# Flight_Computer.net
KiCad netlist of a schematic drawn in EAGLE
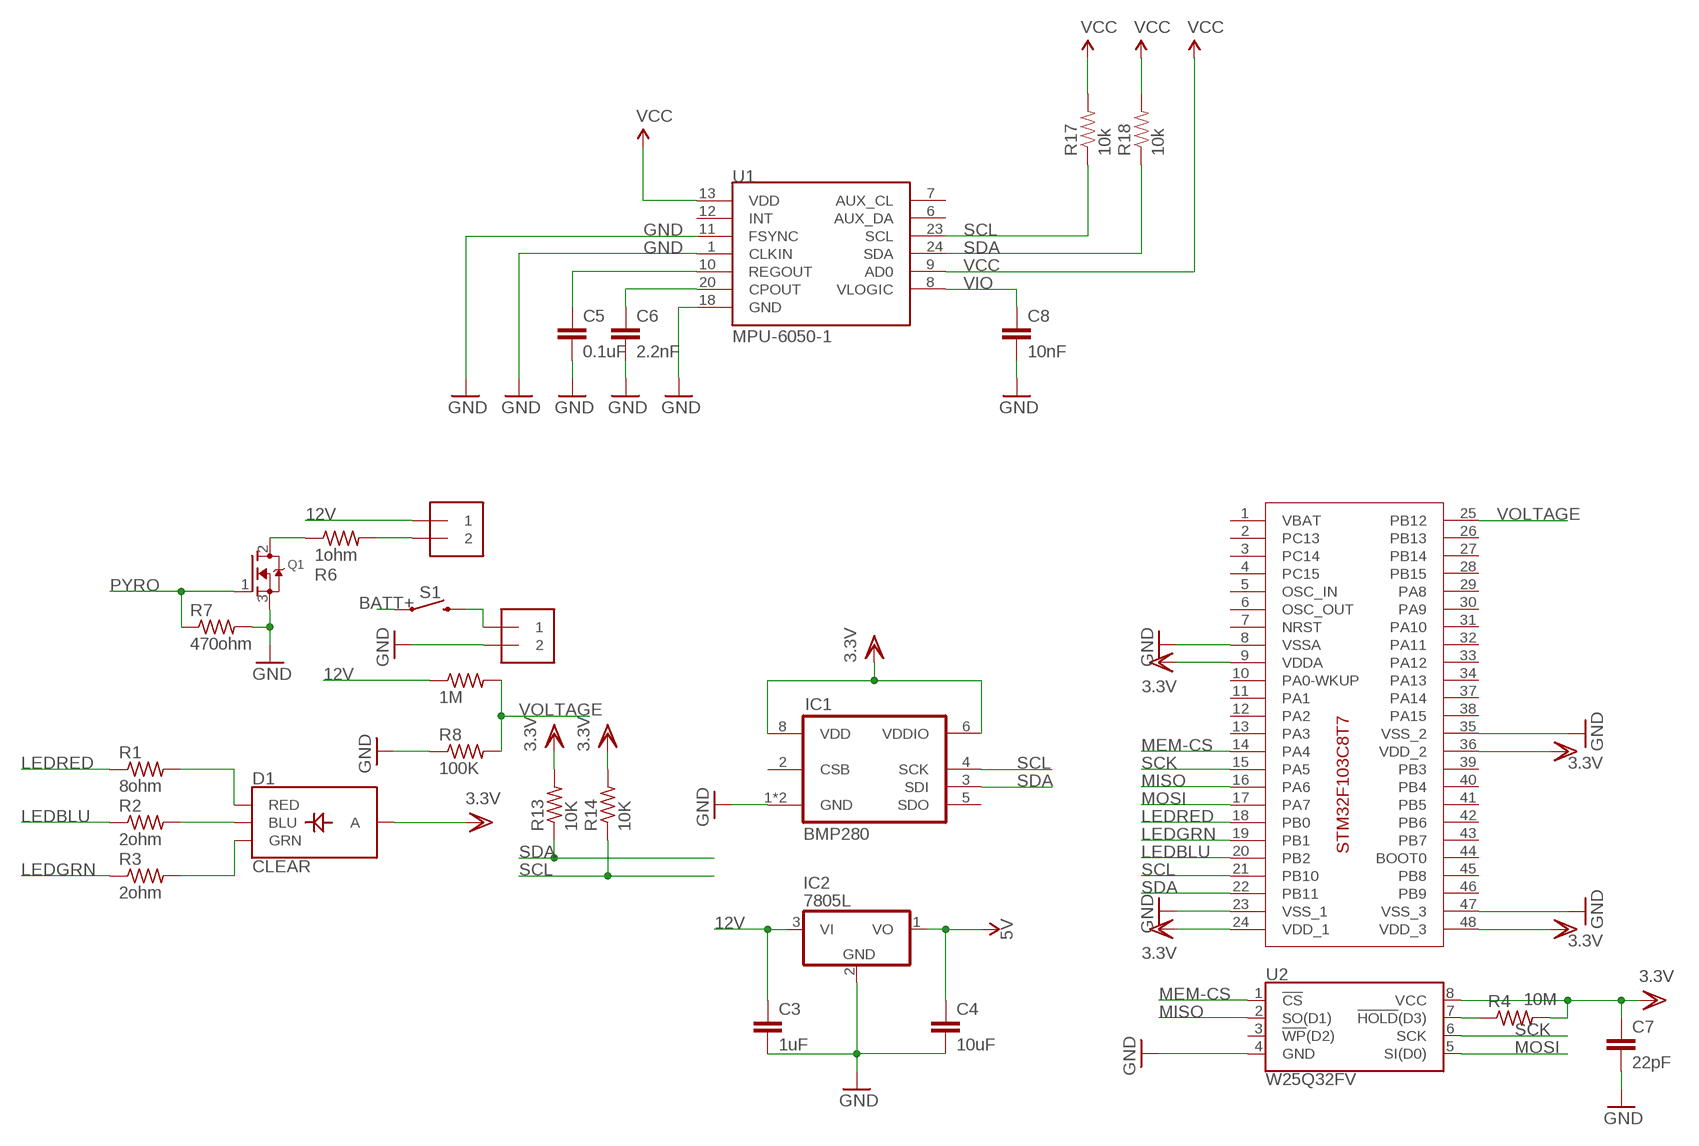
[diagram p0: schematic, sheet 1]

(export (version "E")
  (design (tool "Eeschema 10.0.6"))
  (components
    (comp (ref "C3")
      (value "1uF")
      (footprint "eagle-import:C2.5-3")
      (libsource (lib "eagle-import") (part "C2,5-3"))
    )
    (comp (ref "C4")
      (value "10uF")
      (footprint "eagle-import:C2.5-3")
      (libsource (lib "eagle-import") (part "C2,5-3"))
    )
    (comp (ref "C5")
      (value "0.1uF")
      (footprint "eagle-import:0603-CAP")
      (libsource (lib "eagle-import") (part "CAP0603-CAP"))
    )
    (comp (ref "C6")
      (value "2.2nF")
      (footprint "eagle-import:0603-CAP")
      (libsource (lib "eagle-import") (part "CAP0603-CAP"))
    )
    (comp (ref "C7")
      (value "22pF")
      (footprint "eagle-import:C2.5-3")
      (libsource (lib "eagle-import") (part "C2,5-3"))
    )
    (comp (ref "C8")
      (value "10nF")
      (footprint "eagle-import:0603-CAP")
      (libsource (lib "eagle-import") (part "CAP0603-CAP"))
    )
    (comp (ref "D1")
      (value "CLEAR")
      (footprint "eagle-import:LED-RGB-THRU")
      (libsource (lib "eagle-import") (part "LED-RGB-CACLEAR"))
    )
    (comp (ref "IC1")
      (value "BMP280")
      (footprint "eagle-import:BMP280")
      (libsource (lib "eagle-import") (part "BMP280"))
    )
    (comp (ref "IC2")
      (value "7805L")
      (footprint "eagle-import:TO92")
      (libsource (lib "eagle-import") (part "78L05"))
    )
    (comp (ref "J1")
      (value "1X2-3.5MM")
      (footprint "eagle-import:1X2-3.5MM")
      (libsource (lib "eagle-import") (part "1X2-3.5MM"))
    )
    (comp (ref "J6")
      (value "1X2-3.5MM")
      (footprint "eagle-import:1X2-3.5MM")
      (libsource (lib "eagle-import") (part "1X2-3.5MM"))
    )
    (comp (ref "Q1")
      (value "MOSFET-NGDS_TO220V")
      (footprint "eagle-import:TO220V")
      (libsource (lib "eagle-import") (part "MOSFET-NGDS_TO220V"))
    )
    (comp (ref "R1")
      (value "8ohm")
      (footprint "eagle-import:0204V")
      (libsource (lib "eagle-import") (part "R-US_0204/2V"))
    )
    (comp (ref "R2")
      (value "2ohm")
      (footprint "eagle-import:0204V")
      (libsource (lib "eagle-import") (part "R-US_0204/2V"))
    )
    (comp (ref "R3")
      (value "2ohm")
      (footprint "eagle-import:0204V")
      (libsource (lib "eagle-import") (part "R-US_0204/2V"))
    )
    (comp (ref "R4")
      (value "10M")
      (footprint "eagle-import:0204V")
      (libsource (lib "eagle-import") (part "R-US_0204/2V"))
    )
    (comp (ref "R5")
      (value "1M")
      (footprint "eagle-import:0204V")
      (libsource (lib "eagle-import") (part "R-US_0204/2V"))
    )
    (comp (ref "R6")
      (value "1ohm")
      (footprint "eagle-import:0204V")
      (libsource (lib "eagle-import") (part "R-US_0204/2V"))
    )
    (comp (ref "R7")
      (value "470ohm")
      (footprint "eagle-import:0204V")
      (libsource (lib "eagle-import") (part "R-US_0204/2V"))
    )
    (comp (ref "R8")
      (value "100K")
      (footprint "eagle-import:0204V")
      (libsource (lib "eagle-import") (part "R-US_0204/2V"))
    )
    (comp (ref "R13")
      (value "10K")
      (footprint "eagle-import:0204V")
      (libsource (lib "eagle-import") (part "rcl_334_R-US_0204/2V"))
    )
    (comp (ref "R14")
      (value "10K")
      (footprint "eagle-import:0204V")
      (libsource (lib "eagle-import") (part "rcl_334_R-US_0204/2V"))
    )
    (comp (ref "R17")
      (value "10k")
      (footprint "eagle-import:0603-RES")
      (libsource (lib "eagle-import") (part "RESISTOR0603-RES"))
    )
    (comp (ref "R18")
      (value "10k")
      (footprint "eagle-import:0603-RES")
      (libsource (lib "eagle-import") (part "RESISTOR0603-RES"))
    )
    (comp (ref "S1")
      (value "MOMENTARY-SWITCH-SPST-SMD-5.2-REDUNDANT")
      (footprint "eagle-import:TACTILE_SWITCH_SMD_5.2MM")
      (libsource (lib "eagle-import") (part "MOMENTARY-SWITCH-SPST-SMD-5.2-REDUNDANT"))
    )
    (comp (ref "U$1")
      (value "STM32F103C8T7")
      (footprint "eagle-import:STM32F103C8T7")
      (libsource (lib "eagle-import") (part "STM32F103C8T7"))
    )
    (comp (ref "U1")
      (value "MPU-6050-1")
      (footprint "eagle-import:QFN-24-4MM2")
      (libsource (lib "eagle-import") (part "MPU-6050-1"))
    )
    (comp (ref "U2")
      (value "W25Q32FV")
      (footprint "eagle-import:SOIC-8")
      (libsource (lib "eagle-import") (part "W25Q32FVSS"))
    )
  )
  (nets
    (net (code "1") (name "/12V") (class "Default")
      (node (ref "C3") (pin "1") (pinfunction "1_1") (pintype "passive"))
      (node (ref "IC2") (pin "3") (pinfunction "VI_3") (pintype "input"))
      (node (ref "J6") (pin "1") (pinfunction "1_1") (pintype "passive"))
      (node (ref "R5") (pin "1") (pinfunction "1_1") (pintype "passive"))
    )
    (net (code "2") (name "/BATT+") (class "Default")
      (node (ref "S1") (pin "1") (pinfunction "1_1") (pintype "passive"))
      (node (ref "S1") (pin "2") (pinfunction "1_2") (pintype "passive"))
    )
    (net (code "3") (name "/LEDBLU") (class "Default")
      (node (ref "R2") (pin "1") (pinfunction "1_1") (pintype "passive"))
      (node (ref "U$1") (pin "20") (pinfunction "PB2_20") (pintype "bidirectional"))
    )
    (net (code "4") (name "/LEDGRN") (class "Default")
      (node (ref "R3") (pin "1") (pinfunction "1_1") (pintype "passive"))
      (node (ref "U$1") (pin "19") (pinfunction "PB1_19") (pintype "bidirectional"))
    )
    (net (code "5") (name "/LEDRED") (class "Default")
      (node (ref "R1") (pin "1") (pinfunction "1_1") (pintype "passive"))
      (node (ref "U$1") (pin "18") (pinfunction "PB0_18") (pintype "bidirectional"))
    )
    (net (code "6") (name "/MEM-CS") (class "Default")
      (node (ref "U$1") (pin "14") (pinfunction "PA4_14") (pintype "bidirectional"))
      (node (ref "U2") (pin "1") (pinfunction "~{CS}_1") (pintype "bidirectional"))
    )
    (net (code "7") (name "/MISO") (class "Default")
      (node (ref "U$1") (pin "16") (pinfunction "PA6_16") (pintype "bidirectional"))
      (node (ref "U2") (pin "2") (pinfunction "SO(D1)_2") (pintype "bidirectional"))
    )
    (net (code "8") (name "/MOSI") (class "Default")
      (node (ref "U$1") (pin "17") (pinfunction "PA7_17") (pintype "bidirectional"))
      (node (ref "U2") (pin "5") (pinfunction "SI(D0)_5") (pintype "bidirectional"))
    )
    (net (code "9") (name "/PYRO") (class "Default")
      (node (ref "Q1") (pin "1") (pinfunction "G_1") (pintype "bidirectional"))
      (node (ref "R7") (pin "1") (pinfunction "1_1") (pintype "passive"))
    )
    (net (code "10") (name "/SCK") (class "Default")
      (node (ref "U$1") (pin "15") (pinfunction "PA5_15") (pintype "bidirectional"))
      (node (ref "U2") (pin "6") (pinfunction "SCK_6") (pintype "bidirectional"))
    )
    (net (code "11") (name "/SCL") (class "Default")
      (node (ref "IC1") (pin "4") (pinfunction "SCK_4") (pintype "bidirectional"))
      (node (ref "R14") (pin "1") (pinfunction "1_1") (pintype "passive"))
      (node (ref "R17") (pin "1") (pinfunction "1_1") (pintype "passive"))
      (node (ref "U$1") (pin "21") (pinfunction "PB10_21") (pintype "bidirectional"))
      (node (ref "U1") (pin "23") (pinfunction "SCL_23") (pintype "bidirectional"))
    )
    (net (code "12") (name "/SDA") (class "Default")
      (node (ref "IC1") (pin "3") (pinfunction "SDI_3") (pintype "bidirectional"))
      (node (ref "R13") (pin "1") (pinfunction "1_1") (pintype "passive"))
      (node (ref "R18") (pin "1") (pinfunction "1_1") (pintype "passive"))
      (node (ref "U$1") (pin "22") (pinfunction "PB11_22") (pintype "bidirectional"))
      (node (ref "U1") (pin "24") (pinfunction "SDA_24") (pintype "bidirectional"))
    )
    (net (code "13") (name "/VIO") (class "Default")
      (node (ref "C8") (pin "1") (pinfunction "1_1") (pintype "passive"))
      (node (ref "U1") (pin "8") (pinfunction "VLOGIC_8") (pintype "bidirectional"))
    )
    (net (code "14") (name "/VOLTAGE") (class "Default")
      (node (ref "R5") (pin "2") (pinfunction "2_2") (pintype "passive"))
      (node (ref "R8") (pin "2") (pinfunction "2_2") (pintype "passive"))
      (node (ref "U$1") (pin "25") (pinfunction "PB12_25") (pintype "bidirectional"))
    )
    (net (code "15") (name "3.3V") (class "Default")
      (node (ref "C7") (pin "1") (pinfunction "1_1") (pintype "passive"))
      (node (ref "D1") (pin "2") (pinfunction "A_2") (pintype "bidirectional"))
      (node (ref "IC1") (pin "6") (pinfunction "VDDIO_6") (pintype "power_in"))
      (node (ref "IC1") (pin "8") (pinfunction "VDD_8") (pintype "power_in"))
      (node (ref "R13") (pin "2") (pinfunction "2_2") (pintype "passive"))
      (node (ref "R14") (pin "2") (pinfunction "2_2") (pintype "passive"))
      (node (ref "R4") (pin "2") (pinfunction "2_2") (pintype "passive"))
      (node (ref "U$1") (pin "24") (pinfunction "VDD_1_24") (pintype "bidirectional"))
      (node (ref "U$1") (pin "36") (pinfunction "VDD_2_36") (pintype "bidirectional"))
      (node (ref "U$1") (pin "48") (pinfunction "VDD_3_48") (pintype "bidirectional"))
      (node (ref "U$1") (pin "9") (pinfunction "VDDA_9") (pintype "bidirectional"))
      (node (ref "U2") (pin "8") (pinfunction "VCC_8") (pintype "bidirectional"))
    )
    (net (code "16") (name "5V") (class "Default")
      (node (ref "C4") (pin "1") (pinfunction "1_1") (pintype "passive"))
      (node (ref "IC2") (pin "1") (pinfunction "VO_1") (pintype "passive"))
    )
    (net (code "17") (name "GND") (class "Default")
      (node (ref "C3") (pin "2") (pinfunction "2_2") (pintype "passive"))
      (node (ref "C4") (pin "2") (pinfunction "2_2") (pintype "passive"))
      (node (ref "C5") (pin "2") (pinfunction "2_2") (pintype "passive"))
      (node (ref "C6") (pin "2") (pinfunction "2_2") (pintype "passive"))
      (node (ref "C7") (pin "2") (pinfunction "2_2") (pintype "passive"))
      (node (ref "C8") (pin "2") (pinfunction "2_2") (pintype "passive"))
      (node (ref "IC1") (pin "1") (pinfunction "GND_1") (pintype "power_in"))
      (node (ref "IC1") (pin "7") (pinfunction "GND_7") (pintype "power_in"))
      (node (ref "IC2") (pin "2") (pinfunction "GND_2") (pintype "passive"))
      (node (ref "J1") (pin "2") (pinfunction "2_2") (pintype "passive"))
      (node (ref "Q1") (pin "3") (pinfunction "S_3") (pintype "bidirectional"))
      (node (ref "R7") (pin "2") (pinfunction "2_2") (pintype "passive"))
      (node (ref "R8") (pin "1") (pinfunction "1_1") (pintype "passive"))
      (node (ref "U$1") (pin "23") (pinfunction "VSS_1_23") (pintype "bidirectional"))
      (node (ref "U$1") (pin "35") (pinfunction "VSS_2_35") (pintype "bidirectional"))
      (node (ref "U$1") (pin "47") (pinfunction "VSS_3_47") (pintype "bidirectional"))
      (node (ref "U$1") (pin "8") (pinfunction "VSSA_8") (pintype "bidirectional"))
      (node (ref "U1") (pin "1") (pinfunction "CLKIN_1") (pintype "bidirectional"))
      (node (ref "U1") (pin "11") (pinfunction "FSYNC_11") (pintype "bidirectional"))
      (node (ref "U1") (pin "18") (pinfunction "GND_18") (pintype "bidirectional"))
      (node (ref "U2") (pin "4") (pinfunction "GND_4") (pintype "bidirectional"))
    )
    (net (code "18") (name "Net-(D1-BLU)") (class "Default")
      (node (ref "D1") (pin "4") (pinfunction "BLU_4") (pintype "bidirectional"))
      (node (ref "R2") (pin "2") (pinfunction "2_2") (pintype "passive"))
    )
    (net (code "19") (name "Net-(D1-GRN)") (class "Default")
      (node (ref "D1") (pin "3") (pinfunction "GRN_3") (pintype "bidirectional"))
      (node (ref "R3") (pin "2") (pinfunction "2_2") (pintype "passive"))
    )
    (net (code "20") (name "Net-(D1-RED)") (class "Default")
      (node (ref "D1") (pin "1") (pinfunction "RED_1") (pintype "bidirectional"))
      (node (ref "R1") (pin "2") (pinfunction "2_2") (pintype "passive"))
    )
    (net (code "21") (name "Net-(J1-Pad1)") (class "Default")
      (node (ref "J1") (pin "1") (pinfunction "1_1") (pintype "passive"))
      (node (ref "S1") (pin "3") (pinfunction "2_3") (pintype "passive"))
      (node (ref "S1") (pin "4") (pinfunction "2_4") (pintype "passive"))
    )
    (net (code "22") (name "Net-(J6-Pad2)") (class "Default")
      (node (ref "J6") (pin "2") (pinfunction "2_2") (pintype "passive"))
      (node (ref "R6") (pin "2") (pinfunction "2_2") (pintype "passive"))
    )
    (net (code "23") (name "Net-(Q1-D)") (class "Default")
      (node (ref "Q1") (pin "2") (pinfunction "D_2") (pintype "bidirectional"))
      (node (ref "R6") (pin "1") (pinfunction "1_1") (pintype "passive"))
    )
    (net (code "24") (name "Net-(U1-CPOUT)") (class "Default")
      (node (ref "C6") (pin "1") (pinfunction "1_1") (pintype "passive"))
      (node (ref "U1") (pin "20") (pinfunction "CPOUT_20") (pintype "bidirectional"))
    )
    (net (code "25") (name "Net-(U1-REGOUT)") (class "Default")
      (node (ref "C5") (pin "1") (pinfunction "1_1") (pintype "passive"))
      (node (ref "U1") (pin "10") (pinfunction "REGOUT_10") (pintype "bidirectional"))
    )
    (net (code "26") (name "Net-(U2-~{HOLD}(D3))") (class "Default")
      (node (ref "R4") (pin "1") (pinfunction "1_1") (pintype "passive"))
      (node (ref "U2") (pin "7") (pinfunction "~{HOLD}(D3)_7") (pintype "bidirectional"))
    )
    (net (code "27") (name "VCC") (class "Default")
      (node (ref "R17") (pin "2") (pinfunction "2_2") (pintype "passive"))
      (node (ref "R18") (pin "2") (pinfunction "2_2") (pintype "passive"))
      (node (ref "U1") (pin "13") (pinfunction "VDD_13") (pintype "bidirectional"))
      (node (ref "U1") (pin "9") (pinfunction "AD0_9") (pintype "bidirectional"))
    )
    (net (code "28") (name "unconnected-(IC1-CSB-Pad2)") (class "Default")
      (node (ref "IC1") (pin "2") (pinfunction "CSB_2") (pintype "input"))
    )
    (net (code "29") (name "unconnected-(IC1-SDO-Pad5)") (class "Default")
      (node (ref "IC1") (pin "5") (pinfunction "SDO_5") (pintype "input"))
    )
    (net (code "30") (name "unconnected-(U$1-BOOT0-Pad44)") (class "Default")
      (node (ref "U$1") (pin "44") (pinfunction "BOOT0_44") (pintype "bidirectional"))
    )
    (net (code "31") (name "unconnected-(U$1-NRST-Pad7)") (class "Default")
      (node (ref "U$1") (pin "7") (pinfunction "NRST_7") (pintype "bidirectional"))
    )
    (net (code "32") (name "unconnected-(U$1-OSC_IN-Pad5)") (class "Default")
      (node (ref "U$1") (pin "5") (pinfunction "OSC_IN_5") (pintype "bidirectional"))
    )
    (net (code "33") (name "unconnected-(U$1-OSC_OUT-Pad6)") (class "Default")
      (node (ref "U$1") (pin "6") (pinfunction "OSC_OUT_6") (pintype "bidirectional"))
    )
    (net (code "34") (name "unconnected-(U$1-PA0-WKUP-Pad10)") (class "Default")
      (node (ref "U$1") (pin "10") (pinfunction "PA0-WKUP_10") (pintype "bidirectional"))
    )
    (net (code "35") (name "unconnected-(U$1-PA1-Pad11)") (class "Default")
      (node (ref "U$1") (pin "11") (pinfunction "PA1_11") (pintype "bidirectional"))
    )
    (net (code "36") (name "unconnected-(U$1-PA2-Pad12)") (class "Default")
      (node (ref "U$1") (pin "12") (pinfunction "PA2_12") (pintype "bidirectional"))
    )
    (net (code "37") (name "unconnected-(U$1-PA3-Pad13)") (class "Default")
      (node (ref "U$1") (pin "13") (pinfunction "PA3_13") (pintype "bidirectional"))
    )
    (net (code "38") (name "unconnected-(U$1-PA8-Pad29)") (class "Default")
      (node (ref "U$1") (pin "29") (pinfunction "PA8_29") (pintype "bidirectional"))
    )
    (net (code "39") (name "unconnected-(U$1-PA9-Pad30)") (class "Default")
      (node (ref "U$1") (pin "30") (pinfunction "PA9_30") (pintype "bidirectional"))
    )
    (net (code "40") (name "unconnected-(U$1-PA10-Pad31)") (class "Default")
      (node (ref "U$1") (pin "31") (pinfunction "PA10_31") (pintype "bidirectional"))
    )
    (net (code "41") (name "unconnected-(U$1-PA11-Pad32)") (class "Default")
      (node (ref "U$1") (pin "32") (pinfunction "PA11_32") (pintype "bidirectional"))
    )
    (net (code "42") (name "unconnected-(U$1-PA12-Pad33)") (class "Default")
      (node (ref "U$1") (pin "33") (pinfunction "PA12_33") (pintype "bidirectional"))
    )
    (net (code "43") (name "unconnected-(U$1-PA13-Pad34)") (class "Default")
      (node (ref "U$1") (pin "34") (pinfunction "PA13_34") (pintype "bidirectional"))
    )
    (net (code "44") (name "unconnected-(U$1-PA14-Pad37)") (class "Default")
      (node (ref "U$1") (pin "37") (pinfunction "PA14_37") (pintype "bidirectional"))
    )
    (net (code "45") (name "unconnected-(U$1-PA15-Pad38)") (class "Default")
      (node (ref "U$1") (pin "38") (pinfunction "PA15_38") (pintype "bidirectional"))
    )
    (net (code "46") (name "unconnected-(U$1-PB3-Pad39)") (class "Default")
      (node (ref "U$1") (pin "39") (pinfunction "PB3_39") (pintype "bidirectional"))
    )
    (net (code "47") (name "unconnected-(U$1-PB4-Pad40)") (class "Default")
      (node (ref "U$1") (pin "40") (pinfunction "PB4_40") (pintype "bidirectional"))
    )
    (net (code "48") (name "unconnected-(U$1-PB5-Pad41)") (class "Default")
      (node (ref "U$1") (pin "41") (pinfunction "PB5_41") (pintype "bidirectional"))
    )
    (net (code "49") (name "unconnected-(U$1-PB6-Pad42)") (class "Default")
      (node (ref "U$1") (pin "42") (pinfunction "PB6_42") (pintype "bidirectional"))
    )
    (net (code "50") (name "unconnected-(U$1-PB7-Pad43)") (class "Default")
      (node (ref "U$1") (pin "43") (pinfunction "PB7_43") (pintype "bidirectional"))
    )
    (net (code "51") (name "unconnected-(U$1-PB8-Pad45)") (class "Default")
      (node (ref "U$1") (pin "45") (pinfunction "PB8_45") (pintype "bidirectional"))
    )
    (net (code "52") (name "unconnected-(U$1-PB9-Pad46)") (class "Default")
      (node (ref "U$1") (pin "46") (pinfunction "PB9_46") (pintype "bidirectional"))
    )
    (net (code "53") (name "unconnected-(U$1-PB13-Pad26)") (class "Default")
      (node (ref "U$1") (pin "26") (pinfunction "PB13_26") (pintype "bidirectional"))
    )
    (net (code "54") (name "unconnected-(U$1-PB14-Pad27)") (class "Default")
      (node (ref "U$1") (pin "27") (pinfunction "PB14_27") (pintype "bidirectional"))
    )
    (net (code "55") (name "unconnected-(U$1-PB15-Pad28)") (class "Default")
      (node (ref "U$1") (pin "28") (pinfunction "PB15_28") (pintype "bidirectional"))
    )
    (net (code "56") (name "unconnected-(U$1-PC13-Pad2)") (class "Default")
      (node (ref "U$1") (pin "2") (pinfunction "PC13_2") (pintype "bidirectional"))
    )
    (net (code "57") (name "unconnected-(U$1-PC14-Pad3)") (class "Default")
      (node (ref "U$1") (pin "3") (pinfunction "PC14_3") (pintype "bidirectional"))
    )
    (net (code "58") (name "unconnected-(U$1-PC15-Pad4)") (class "Default")
      (node (ref "U$1") (pin "4") (pinfunction "PC15_4") (pintype "bidirectional"))
    )
    (net (code "59") (name "unconnected-(U$1-VBAT-Pad1)") (class "Default")
      (node (ref "U$1") (pin "1") (pinfunction "VBAT_1") (pintype "bidirectional"))
    )
    (net (code "60") (name "unconnected-(U1-AUX_CL-Pad7)") (class "Default")
      (node (ref "U1") (pin "7") (pinfunction "AUX_CL_7") (pintype "bidirectional"))
    )
    (net (code "61") (name "unconnected-(U1-AUX_DA-Pad6)") (class "Default")
      (node (ref "U1") (pin "6") (pinfunction "AUX_DA_6") (pintype "bidirectional"))
    )
    (net (code "62") (name "unconnected-(U1-INT-Pad12)") (class "Default")
      (node (ref "U1") (pin "12") (pinfunction "INT_12") (pintype "bidirectional"))
    )
    (net (code "63") (name "unconnected-(U2-~{WP}(D2)-Pad3)") (class "Default")
      (node (ref "U2") (pin "3") (pinfunction "~{WP}(D2)_3") (pintype "bidirectional"))
    )
  )
)
